# design.net
KiCad netlist of a schematic drawn in Altium Designer
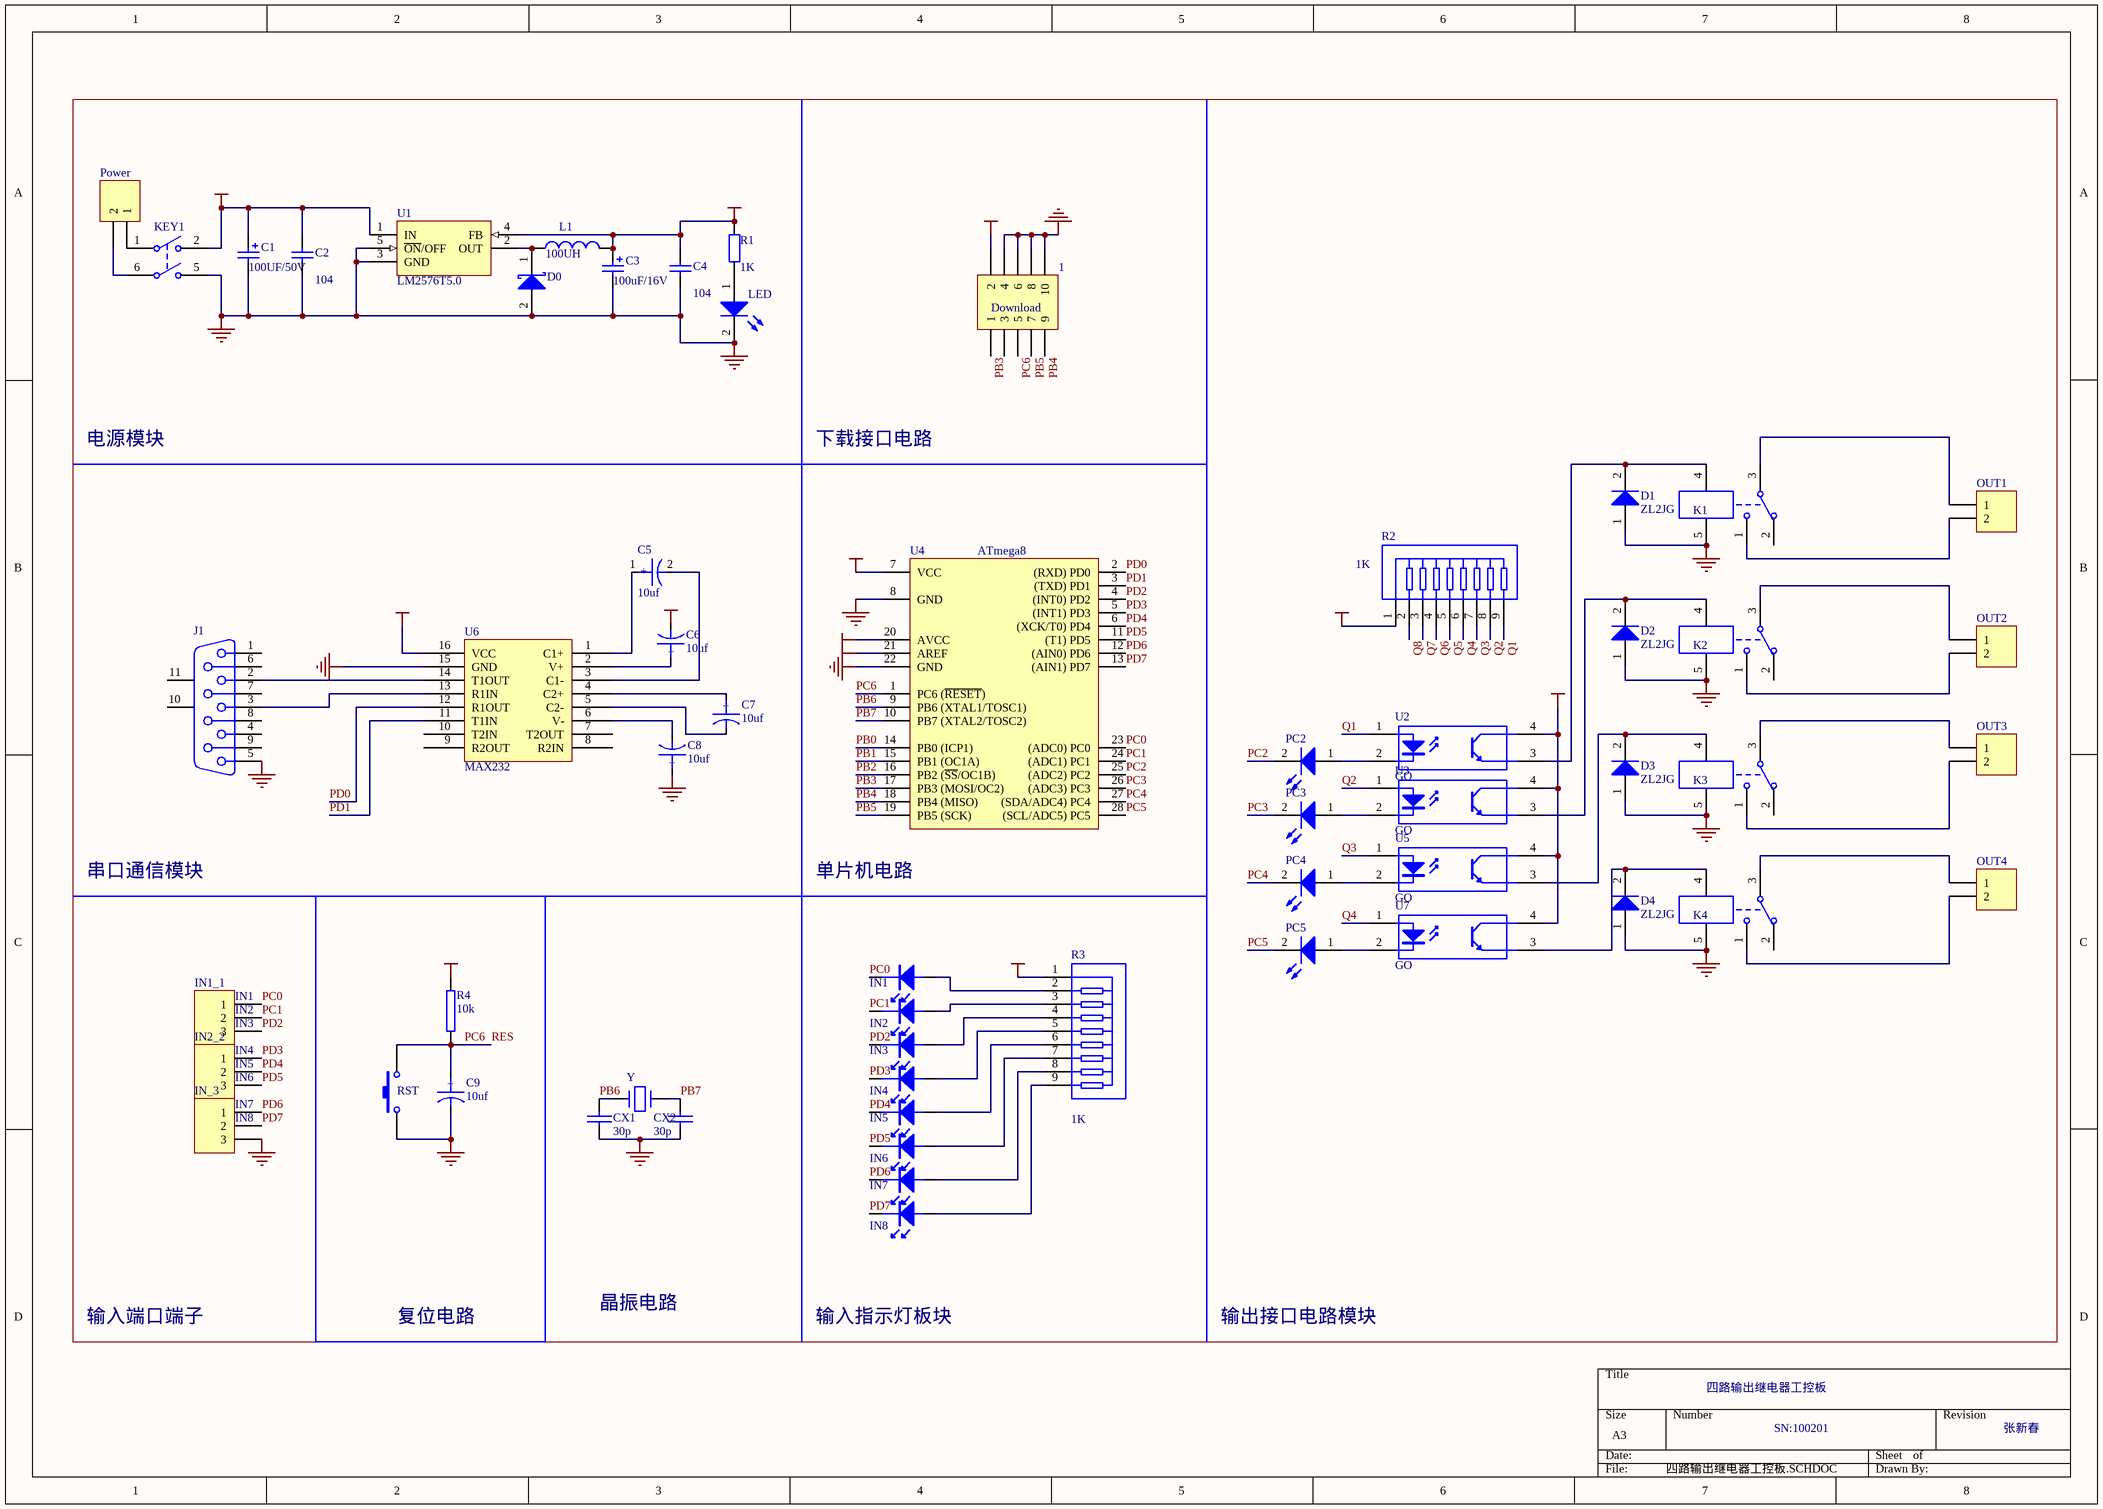
[diagram p0: 四路输出继电器工控板.SCHDOC]

(export (version "E")
  (design (tool "Eeschema 10.0.6"))
  (components
    (comp (ref "1")
      (value "Download")
      (footprint "HDR-2x5")
      (description "Header, 5-Pin, Dual row")
      (fields (field (name "PUBLISHER") "Altium Limited"))
      (libsource (lib "Miscellaneous Connectors") (part "Header 5X2"))
    )
    (comp (ref "C1")
      (value "100UF/50V")
      (footprint "C-DJ-6")
      (description "电解电容")
      (fields (field (name "Comment") "DJDR") (field (name "PUBLISHER") "Altium Limited"))
      (libsource (lib "zxcourhc") (part "DJDR"))
    )
    (comp (ref "C2")
      (value "104")
      (footprint "CPDR")
      (description "瓷片电容")
      (fields (field (name "Comment") "CPDR") (field (name "PUBLISHER") "Altium Limited"))
      (libsource (lib "zxcourhc") (part "CPDR"))
    )
    (comp (ref "C3")
      (value "100uF/16V")
      (footprint "C-DJ-6")
      (description "电解电容")
      (fields (field (name "Comment") "DJDR") (field (name "PUBLISHER") "Altium Limited"))
      (libsource (lib "zxcourhc") (part "DJDR"))
    )
    (comp (ref "C4")
      (value "104")
      (footprint "CPDR")
      (description "瓷片电容")
      (fields (field (name "Comment") "CPDR") (field (name "PUBLISHER") "Altium Limited"))
      (libsource (lib "zxcourhc") (part "CPDR"))
    )
    (comp (ref "C5")
      (value "10uf")
      (footprint "C-DJ-4")
      (description "Capacitor")
      (libsource (lib "*") (part "CAPACITOR POL"))
    )
    (comp (ref "C6")
      (value "10uf")
      (footprint "C-DJ-4")
      (description "Capacitor")
      (libsource (lib "") (part "CAPACITOR POL_1"))
    )
    (comp (ref "C7")
      (value "10uf")
      (footprint "C-DJ-4")
      (description "Capacitor")
      (libsource (lib "") (part "CAPACITOR POL_1"))
    )
    (comp (ref "C8")
      (value "10uf")
      (footprint "C-DJ-4")
      (description "Capacitor")
      (libsource (lib "") (part "CAPACITOR POL_1"))
    )
    (comp (ref "C9")
      (value "10uf")
      (footprint "C-DJ-4")
      (description "Capacitor")
      (libsource (lib "") (part "CAPACITOR POL_1"))
    )
    (comp (ref "CX1")
      (value "30p")
      (footprint "HDR1X2")
      (description "Capacitor")
      (libsource (lib "*") (part "CAP"))
    )
    (comp (ref "CX2")
      (value "30p")
      (footprint "HDR1X2")
      (description "Capacitor")
      (libsource (lib "*") (part "CAP"))
    )
    (comp (ref "D0")
      (value "WY2JG")
      (footprint "ZCDZL")
      (description "稳压二级管")
      (fields (field (name "PUBLISHER") "Altium Limited"))
      (libsource (lib "zxcourhc") (part "WY2JG"))
    )
    (comp (ref "D1")
      (value "ZL2JG")
      (footprint "D-ZL-10")
      (description "整流二极管")
      (fields (field (name "PUBLISHER") "Altium Limited"))
      (libsource (lib "zxcourhc") (part "ZL2JG"))
    )
    (comp (ref "D2")
      (value "ZL2JG")
      (footprint "D-ZL-10")
      (description "整流二极管")
      (fields (field (name "PUBLISHER") "Altium Limited"))
      (libsource (lib "zxcourhc") (part "ZL2JG"))
    )
    (comp (ref "D3")
      (value "ZL2JG")
      (footprint "D-ZL-10")
      (description "整流二极管")
      (fields (field (name "PUBLISHER") "Altium Limited"))
      (libsource (lib "zxcourhc") (part "ZL2JG"))
    )
    (comp (ref "D4")
      (value "ZL2JG")
      (footprint "D-ZL-10")
      (description "整流二极管")
      (fields (field (name "PUBLISHER") "Altium Limited"))
      (libsource (lib "zxcourhc") (part "ZL2JG"))
    )
    (comp (ref "IN1") (value "LED") (footprint "HDR1X2") (libsource (lib "OldCow1 (1)") (part "LED")))
    (comp (ref "IN1_1")
      (value "PZ_3")
      (footprint "JK128_3")
      (description "排针——3")
      (fields (field (name "PUBLISHER") "Altium Limited"))
      (libsource (lib "zxcourhc") (part "PZ_3"))
    )
    (comp (ref "IN2") (value "LED") (footprint "HDR1X2") (libsource (lib "OldCow1 (1)") (part "LED")))
    (comp (ref "IN2_2")
      (value "PZ_3")
      (footprint "JK128_3")
      (description "排针——3")
      (fields (field (name "PUBLISHER") "Altium Limited"))
      (libsource (lib "zxcourhc") (part "PZ_3"))
    )
    (comp (ref "IN3") (value "LED") (footprint "HDR1X2") (libsource (lib "OldCow1 (1)") (part "LED")))
    (comp (ref "IN4") (value "LED") (footprint "HDR1X2") (libsource (lib "OldCow1 (1)") (part "LED")))
    (comp (ref "IN5") (value "LED") (footprint "HDR1X2") (libsource (lib "OldCow1 (1)") (part "LED")))
    (comp (ref "IN6") (value "LED") (footprint "HDR1X2") (libsource (lib "OldCow1 (1)") (part "LED")))
    (comp (ref "IN7") (value "LED") (footprint "HDR1X2") (libsource (lib "OldCow1 (1)") (part "LED")))
    (comp (ref "IN8") (value "LED") (footprint "HDR1X2") (libsource (lib "OldCow1 (1)") (part "LED")))
    (comp (ref "IN_3")
      (value "~")
      (footprint "JK128_3")
      (description "排针——3")
      (fields (field (name "PUBLISHER") "Altium Limited"))
      (libsource (lib "zxcourhc") (part "PZ_3"))
    )
    (comp (ref "J1")
      (value "D Connector 9")
      (footprint "DSUB1.385-2H9")
      (description "Receptacle Assembly, 9 Position, Right Angle")
      (fields (field (name "PUBLISHER") "Altium Limited"))
      (libsource (lib "Miscellaneous Connectors") (part "D Connector 9"))
    )
    (comp (ref "K1")
      (value "JDQYCK")
      (footprint "JQC-3F/T73")
      (description "继电器——1常开1常闭")
      (fields (field (name "PUBLISHER") "Altium Limited"))
      (libsource (lib "zxcourhc") (part "JDQYCK"))
    )
    (comp (ref "K2")
      (value "JDQYCK")
      (footprint "JQC-3F/T73")
      (description "继电器——1常开1常闭")
      (fields (field (name "PUBLISHER") "Altium Limited"))
      (libsource (lib "zxcourhc") (part "JDQYCK"))
    )
    (comp (ref "K3")
      (value "JDQYCK")
      (footprint "JQC-3F/T73")
      (description "继电器——1常开1常闭")
      (fields (field (name "PUBLISHER") "Altium Limited"))
      (libsource (lib "zxcourhc") (part "JDQYCK"))
    )
    (comp (ref "K4")
      (value "JDQYCK")
      (footprint "JQC-3F/T73")
      (description "继电器——1常开1常闭")
      (fields (field (name "PUBLISHER") "Altium Limited"))
      (libsource (lib "zxcourhc") (part "JDQYCK"))
    )
    (comp (ref "KEY1")
      (value "SW-DPST")
      (footprint "DPDT-6")
      (description "Double-Pole, Single-Throw Switch")
      (fields (field (name "PUBLISHER") "Altium Limited"))
      (libsource (lib "Miscellaneous Devices") (part "SW-DPST"))
    )
    (comp (ref "L1")
      (value "100UH")
      (footprint "L_DG")
      (description "电感")
      (fields (field (name "Comment") "DG") (field (name "PUBLISHER") "Altium Limited"))
      (libsource (lib "zxcourhc") (part "DG"))
    )
    (comp (ref "LED")
      (value "LED")
      (footprint "LED_D")
      (description "发光二极管")
      (fields (field (name "PUBLISHER") "Altium Limited"))
      (libsource (lib "zxcourhc") (part "LED"))
    )
    (comp (ref "OUT1")
      (value "PZ_2")
      (footprint "DYDZ")
      (description "排针——2")
      (fields (field (name "PUBLISHER") "Altium Limited"))
      (libsource (lib "zxcourhc") (part "PZ_2"))
    )
    (comp (ref "OUT2")
      (value "PZ_2")
      (footprint "DYDZ")
      (description "排针——2")
      (fields (field (name "PUBLISHER") "Altium Limited"))
      (libsource (lib "zxcourhc") (part "PZ_2"))
    )
    (comp (ref "OUT3")
      (value "PZ_2")
      (footprint "DYDZ")
      (description "排针——2")
      (fields (field (name "PUBLISHER") "Altium Limited"))
      (libsource (lib "zxcourhc") (part "PZ_2"))
    )
    (comp (ref "OUT4")
      (value "PZ_2")
      (footprint "DYDZ")
      (description "排针——2")
      (fields (field (name "PUBLISHER") "Altium Limited"))
      (libsource (lib "zxcourhc") (part "PZ_2"))
    )
    (comp (ref "PC2")
      (value "~")
      (footprint "CPDR")
      (description "发光二极管")
      (fields (field (name "PUBLISHER") "Altium Limited"))
      (libsource (lib "zxcourhc") (part "LED"))
    )
    (comp (ref "PC3")
      (value "~")
      (footprint "CPDR")
      (description "发光二极管")
      (fields (field (name "PUBLISHER") "Altium Limited"))
      (libsource (lib "zxcourhc") (part "LED"))
    )
    (comp (ref "PC4")
      (value "~")
      (footprint "CPDR")
      (description "发光二极管")
      (fields (field (name "PUBLISHER") "Altium Limited"))
      (libsource (lib "zxcourhc") (part "LED"))
    )
    (comp (ref "PC5")
      (value "~")
      (footprint "CPDR")
      (description "发光二极管")
      (fields (field (name "PUBLISHER") "Altium Limited"))
      (libsource (lib "zxcourhc") (part "LED"))
    )
    (comp (ref "Power")
      (value "PZ_2")
      (footprint "JK128_2")
      (description "排针——2")
      (fields (field (name "PUBLISHER") "Altium Limited"))
      (libsource (lib "") (part "PZ_2_1"))
    )
    (comp (ref "R1")
      (value "1K")
      (footprint "RSE")
      (description "电阻")
      (fields (field (name "Comment") "Res") (field (name "PUBLISHER") "Altium Limited"))
      (libsource (lib "zxcourhc") (part "Res"))
    )
    (comp (ref "R2")
      (value "1K")
      (footprint "HDR-10")
      (description "8位排阻")
      (fields (field (name "PUBLISHER") "Altium Limited"))
      (libsource (lib "zxcourhc") (part "Res PZ_8"))
    )
    (comp (ref "R3")
      (value "1K")
      (footprint "HDR-10")
      (description "8位排阻")
      (fields (field (name "PUBLISHER") "Altium Limited"))
      (libsource (lib "zxcourhc") (part "Res PZ_8"))
    )
    (comp (ref "R4") (value "10k") (footprint "RSE") (libsource (lib "*") (part "RES2")))
    (comp (ref "RST")
      (value "~")
      (footprint "an-6*6")
      (description "Switch")
      (fields (field (name "PUBLISHER") "Altium Limited"))
      (libsource (lib "Miscellaneous Devices") (part "SW-PB"))
    )
    (comp (ref "U1")
      (value "LM2576T5.0")
      (footprint "LM2576")
      (description "Simple Switcher 3A Step Down Voltage Regulator")
      (fields (field (name "PUBLISHER") "Altium Limited"))
      (libsource (lib "NSC Power Mgt Switching Regulator") (part "LM2576HVT-3.3"))
    )
    (comp (ref "U2")
      (value "GO")
      (footprint "DIP-4")
      (description "光耦")
      (fields (field (name "PUBLISHER") "Altium Limited"))
      (libsource (lib "zxcourhc") (part "GO"))
    )
    (comp (ref "U3")
      (value "GO")
      (footprint "DIP-4")
      (description "光耦")
      (fields (field (name "PUBLISHER") "Altium Limited"))
      (libsource (lib "zxcourhc") (part "GO"))
    )
    (comp (ref "U4")
      (value "ATmega8")
      (footprint "DIP-28")
      (description "8 位微处理器/28引脚")
      (fields (field (name "发布者") "磊元工作室"))
      (libsource (lib "MCU") (part "ATmega8-P"))
    )
    (comp (ref "U5")
      (value "GO")
      (footprint "DIP-4")
      (description "光耦")
      (fields (field (name "PUBLISHER") "Altium Limited"))
      (libsource (lib "zxcourhc") (part "GO"))
    )
    (comp (ref "U6") (value "MAX232") (footprint "DIP16") (libsource (lib "*") (part "MAX232")))
    (comp (ref "U7")
      (value "GO")
      (footprint "DIP-4")
      (description "光耦")
      (fields (field (name "PUBLISHER") "Altium Limited"))
      (libsource (lib "zxcourhc") (part "GO"))
    )
    (comp (ref "Y1")
      (value "Y")
      (footprint "JZ_ZC")
      (description "Crystal")
      (libsource (lib "*") (part "CRYSTAL"))
    )
  )
  (nets
    (net (code "1") (name "+12V") (class "Default")
      (node (ref "C1") (pin "1") (pinfunction "1_1") (pintype "passive"))
      (node (ref "C2") (pin "2") (pinfunction "2_2") (pintype "passive"))
      (node (ref "KEY1") (pin "2") (pinfunction "NO1_2") (pintype "passive"))
      (node (ref "U1") (pin "1") (pinfunction "IN_1") (pintype "power_in"))
      (node (ref "U2") (pin "4") (pinfunction "C_4") (pintype "passive"))
      (node (ref "U3") (pin "4") (pinfunction "C_4") (pintype "passive"))
      (node (ref "U5") (pin "4") (pinfunction "C_4") (pintype "passive"))
      (node (ref "U7") (pin "4") (pinfunction "C_4") (pintype "passive"))
    )
    (net (code "2") (name "/PB0") (class "Default")
      (node (ref "U4") (pin "14") (pinfunction "PB0_(ICP1)_14") (pintype "passive"))
    )
    (net (code "3") (name "/PB1") (class "Default")
      (node (ref "U4") (pin "15") (pinfunction "PB1_(OC1A)_15") (pintype "passive"))
    )
    (net (code "4") (name "/PB2") (class "Default")
      (node (ref "U4") (pin "16") (pinfunction "PB2_(~{SS}/OC1B)_16") (pintype "passive"))
    )
    (net (code "5") (name "/PB3") (class "Default")
      (node (ref "1") (pin "1") (pinfunction "1_1") (pintype "passive"))
      (node (ref "U4") (pin "17") (pinfunction "PB3_(MOSI/OC2)_17") (pintype "passive"))
    )
    (net (code "6") (name "/PB4") (class "Default")
      (node (ref "1") (pin "9") (pinfunction "9_9") (pintype "passive"))
      (node (ref "U4") (pin "18") (pinfunction "PB4_(MISO)_18") (pintype "passive"))
    )
    (net (code "7") (name "/PB5") (class "Default")
      (node (ref "1") (pin "7") (pinfunction "7_7") (pintype "passive"))
      (node (ref "U4") (pin "19") (pinfunction "PB5_(SCK)_19") (pintype "passive"))
    )
    (net (code "8") (name "/PB6") (class "Default")
      (node (ref "CX1") (pin "1") (pinfunction "1_1") (pintype "passive"))
      (node (ref "U4") (pin "9") (pinfunction "PB6_(XTAL1/TOSC1)_9") (pintype "passive"))
      (node (ref "Y1") (pin "2") (pinfunction "2_2") (pintype "passive"))
    )
    (net (code "9") (name "/PB7") (class "Default")
      (node (ref "CX2") (pin "1") (pinfunction "1_1") (pintype "passive"))
      (node (ref "U4") (pin "10") (pinfunction "PB7_(XTAL2/TOSC2)_10") (pintype "passive"))
      (node (ref "Y1") (pin "1") (pinfunction "1_1") (pintype "passive"))
    )
    (net (code "10") (name "/PC0") (class "Default")
      (node (ref "IN1") (pin "2") (pinfunction "K_2") (pintype "passive"))
      (node (ref "IN1_1") (pin "1") (pinfunction "1_1") (pintype "passive"))
      (node (ref "U4") (pin "23") (pinfunction "(ADC0)_PC0_23") (pintype "passive"))
    )
    (net (code "11") (name "/PC1") (class "Default")
      (node (ref "IN1_1") (pin "2") (pinfunction "2_2") (pintype "passive"))
      (node (ref "IN2") (pin "2") (pinfunction "K_2") (pintype "passive"))
      (node (ref "U4") (pin "24") (pinfunction "(ADC1)_PC1_24") (pintype "passive"))
    )
    (net (code "12") (name "/PC2") (class "Default")
      (node (ref "PC2") (pin "2") (pinfunction "K_2") (pintype "passive"))
      (node (ref "U4") (pin "25") (pinfunction "(ADC2)_PC2_25") (pintype "passive"))
    )
    (net (code "13") (name "/PC3") (class "Default")
      (node (ref "PC3") (pin "2") (pinfunction "K_2") (pintype "passive"))
      (node (ref "U4") (pin "26") (pinfunction "(ADC3)_PC3_26") (pintype "passive"))
    )
    (net (code "14") (name "/PC4") (class "Default")
      (node (ref "PC4") (pin "2") (pinfunction "K_2") (pintype "passive"))
      (node (ref "U4") (pin "27") (pinfunction "(SDA/ADC4)_PC4_27") (pintype "passive"))
    )
    (net (code "15") (name "/PC5") (class "Default")
      (node (ref "PC5") (pin "2") (pinfunction "K_2") (pintype "passive"))
      (node (ref "U4") (pin "28") (pinfunction "(SCL/ADC5)_PC5_28") (pintype "passive"))
    )
    (net (code "16") (name "/PC6") (class "Default")
      (node (ref "1") (pin "5") (pinfunction "5_5") (pintype "passive"))
      (node (ref "C9") (pin "1") (pinfunction "1_1") (pintype "passive"))
      (node (ref "R4") (pin "1") (pinfunction "1_1") (pintype "passive"))
      (node (ref "RST") (pin "1") (pinfunction "1_1") (pintype "passive"))
      (node (ref "U4") (pin "1") (pinfunction "PC6_(~{RESET})_1") (pintype "passive"))
    )
    (net (code "17") (name "/PD0") (class "Default")
      (node (ref "U4") (pin "2") (pinfunction "(RXD)_PD0_2") (pintype "passive"))
      (node (ref "U6") (pin "12") (pinfunction "R1OUT_12") (pintype "passive"))
    )
    (net (code "18") (name "/PD1") (class "Default")
      (node (ref "U4") (pin "3") (pinfunction "(TXD)_PD1_3") (pintype "passive"))
      (node (ref "U6") (pin "11") (pinfunction "T1IN_11") (pintype "passive"))
    )
    (net (code "19") (name "/PD2") (class "Default")
      (node (ref "IN1_1") (pin "3") (pinfunction "3_3") (pintype "passive"))
      (node (ref "IN3") (pin "2") (pinfunction "K_2") (pintype "passive"))
      (node (ref "U4") (pin "4") (pinfunction "(INT0)_PD2_4") (pintype "passive"))
    )
    (net (code "20") (name "/PD3") (class "Default")
      (node (ref "IN2_2") (pin "1") (pinfunction "1_1") (pintype "passive"))
      (node (ref "IN4") (pin "2") (pinfunction "K_2") (pintype "passive"))
      (node (ref "U4") (pin "5") (pinfunction "(INT1)_PD3_5") (pintype "passive"))
    )
    (net (code "21") (name "/PD4") (class "Default")
      (node (ref "IN2_2") (pin "2") (pinfunction "2_2") (pintype "passive"))
      (node (ref "IN5") (pin "2") (pinfunction "K_2") (pintype "passive"))
      (node (ref "U4") (pin "6") (pinfunction "(XCK/T0)_PD4_6") (pintype "passive"))
    )
    (net (code "22") (name "/PD5") (class "Default")
      (node (ref "IN2_2") (pin "3") (pinfunction "3_3") (pintype "passive"))
      (node (ref "IN6") (pin "2") (pinfunction "K_2") (pintype "passive"))
      (node (ref "U4") (pin "11") (pinfunction "(T1)_PD5_11") (pintype "passive"))
    )
    (net (code "23") (name "/PD6") (class "Default")
      (node (ref "IN7") (pin "2") (pinfunction "K_2") (pintype "passive"))
      (node (ref "IN_3") (pin "1") (pinfunction "1_1") (pintype "passive"))
      (node (ref "U4") (pin "12") (pinfunction "(AIN0)_PD6_12") (pintype "passive"))
    )
    (net (code "24") (name "/PD7") (class "Default")
      (node (ref "IN8") (pin "2") (pinfunction "K_2") (pintype "passive"))
      (node (ref "IN_3") (pin "2") (pinfunction "2_2") (pintype "passive"))
      (node (ref "U4") (pin "13") (pinfunction "(AIN1)_PD7_13") (pintype "passive"))
    )
    (net (code "25") (name "/Q1") (class "Default")
      (node (ref "R2") (pin "9") (pinfunction "9_9") (pintype "passive"))
      (node (ref "U2") (pin "1") (pinfunction "A_1") (pintype "passive"))
    )
    (net (code "26") (name "/Q2") (class "Default")
      (node (ref "R2") (pin "8") (pinfunction "8_8") (pintype "passive"))
      (node (ref "U3") (pin "1") (pinfunction "A_1") (pintype "passive"))
    )
    (net (code "27") (name "/Q3") (class "Default")
      (node (ref "R2") (pin "7") (pinfunction "7_7") (pintype "passive"))
      (node (ref "U5") (pin "1") (pinfunction "A_1") (pintype "passive"))
    )
    (net (code "28") (name "/Q4") (class "Default")
      (node (ref "R2") (pin "6") (pinfunction "6_6") (pintype "passive"))
      (node (ref "U7") (pin "1") (pinfunction "A_1") (pintype "passive"))
    )
    (net (code "29") (name "/Q5") (class "Default")
      (node (ref "R2") (pin "5") (pinfunction "5_5") (pintype "passive"))
    )
    (net (code "30") (name "/Q6") (class "Default")
      (node (ref "R2") (pin "4") (pinfunction "4_4") (pintype "passive"))
    )
    (net (code "31") (name "/Q7") (class "Default")
      (node (ref "R2") (pin "3") (pinfunction "3_3") (pintype "passive"))
    )
    (net (code "32") (name "/Q8") (class "Default")
      (node (ref "R2") (pin "2") (pinfunction "2_2") (pintype "passive"))
    )
    (net (code "33") (name "GND") (class "Default")
      (node (ref "1") (pin "10") (pinfunction "10_10") (pintype "passive"))
      (node (ref "1") (pin "4") (pinfunction "4_4") (pintype "passive"))
      (node (ref "1") (pin "6") (pinfunction "6_6") (pintype "passive"))
      (node (ref "1") (pin "8") (pinfunction "8_8") (pintype "passive"))
      (node (ref "C1") (pin "2") (pinfunction "2_2") (pintype "passive"))
      (node (ref "C2") (pin "1") (pinfunction "1_1") (pintype "passive"))
      (node (ref "C3") (pin "2") (pinfunction "2_2") (pintype "passive"))
      (node (ref "C4") (pin "1") (pinfunction "1_1") (pintype "passive"))
      (node (ref "C8") (pin "1") (pinfunction "1_1") (pintype "passive"))
      (node (ref "C9") (pin "2") (pinfunction "2_2") (pintype "passive"))
      (node (ref "CX1") (pin "2") (pinfunction "2_2") (pintype "passive"))
      (node (ref "CX2") (pin "2") (pinfunction "2_2") (pintype "passive"))
      (node (ref "D0") (pin "2") (pinfunction "K_2") (pintype "passive"))
      (node (ref "D1") (pin "1") (pinfunction "A_1") (pintype "passive"))
      (node (ref "D2") (pin "1") (pinfunction "A_1") (pintype "passive"))
      (node (ref "D3") (pin "1") (pinfunction "A_1") (pintype "passive"))
      (node (ref "D4") (pin "1") (pinfunction "A_1") (pintype "passive"))
      (node (ref "IN_3") (pin "3") (pinfunction "3_3") (pintype "passive"))
      (node (ref "J1") (pin "5") (pinfunction "5_5") (pintype "passive"))
      (node (ref "K1") (pin "5") (pinfunction "5_5") (pintype "passive"))
      (node (ref "K2") (pin "5") (pinfunction "5_5") (pintype "passive"))
      (node (ref "K3") (pin "5") (pinfunction "5_5") (pintype "passive"))
      (node (ref "K4") (pin "5") (pinfunction "5_5") (pintype "passive"))
      (node (ref "KEY1") (pin "5") (pinfunction "NO2_5") (pintype "passive"))
      (node (ref "LED") (pin "2") (pinfunction "K_2") (pintype "passive"))
      (node (ref "RST") (pin "2") (pinfunction "2_2") (pintype "passive"))
      (node (ref "U1") (pin "3") (pinfunction "GND_3") (pintype "power_in"))
      (node (ref "U1") (pin "5") (pinfunction "~{ON}/OFF_5") (pintype "input"))
      (node (ref "U4") (pin "22") (pinfunction "GND_22") (pintype "passive"))
      (node (ref "U4") (pin "8") (pinfunction "GND_8") (pintype "passive"))
      (node (ref "U6") (pin "15") (pinfunction "GND_15") (pintype "passive"))
    )
    (net (code "34") (name "Net-(D0-A)") (class "Default")
      (node (ref "D0") (pin "1") (pinfunction "A_1") (pintype "passive"))
      (node (ref "L1") (pin "1") (pinfunction "1_1") (pintype "passive"))
      (node (ref "U1") (pin "2") (pinfunction "OUT_2") (pintype "power_in"))
    )
    (net (code "35") (name "Net-(D1-K)") (class "Default")
      (node (ref "D1") (pin "2") (pinfunction "K_2") (pintype "passive"))
      (node (ref "K1") (pin "4") (pinfunction "4_4") (pintype "passive"))
      (node (ref "U2") (pin "3") (pinfunction "E_3") (pintype "passive"))
    )
    (net (code "36") (name "Net-(D2-K)") (class "Default")
      (node (ref "D2") (pin "2") (pinfunction "K_2") (pintype "passive"))
      (node (ref "K2") (pin "4") (pinfunction "4_4") (pintype "passive"))
      (node (ref "U3") (pin "3") (pinfunction "E_3") (pintype "passive"))
    )
    (net (code "37") (name "Net-(D3-K)") (class "Default")
      (node (ref "D3") (pin "2") (pinfunction "K_2") (pintype "passive"))
      (node (ref "K3") (pin "4") (pinfunction "4_4") (pintype "passive"))
      (node (ref "U5") (pin "3") (pinfunction "E_3") (pintype "passive"))
    )
    (net (code "38") (name "Net-(D4-K)") (class "Default")
      (node (ref "D4") (pin "2") (pinfunction "K_2") (pintype "passive"))
      (node (ref "K4") (pin "4") (pinfunction "4_4") (pintype "passive"))
      (node (ref "U7") (pin "3") (pinfunction "E_3") (pintype "passive"))
    )
    (net (code "39") (name "Net-(IN1-A)") (class "Default")
      (node (ref "IN1") (pin "1") (pinfunction "A_1") (pintype "passive"))
      (node (ref "R3") (pin "2") (pinfunction "2_2") (pintype "passive"))
    )
    (net (code "40") (name "Net-(IN2-A)") (class "Default")
      (node (ref "IN2") (pin "1") (pinfunction "A_1") (pintype "passive"))
      (node (ref "R3") (pin "3") (pinfunction "3_3") (pintype "passive"))
    )
    (net (code "41") (name "Net-(IN3-A)") (class "Default")
      (node (ref "IN3") (pin "1") (pinfunction "A_1") (pintype "passive"))
      (node (ref "R3") (pin "4") (pinfunction "4_4") (pintype "passive"))
    )
    (net (code "42") (name "Net-(IN4-A)") (class "Default")
      (node (ref "IN4") (pin "1") (pinfunction "A_1") (pintype "passive"))
      (node (ref "R3") (pin "5") (pinfunction "5_5") (pintype "passive"))
    )
    (net (code "43") (name "Net-(IN5-A)") (class "Default")
      (node (ref "IN5") (pin "1") (pinfunction "A_1") (pintype "passive"))
      (node (ref "R3") (pin "6") (pinfunction "6_6") (pintype "passive"))
    )
    (net (code "44") (name "Net-(IN6-A)") (class "Default")
      (node (ref "IN6") (pin "1") (pinfunction "A_1") (pintype "passive"))
      (node (ref "R3") (pin "7") (pinfunction "7_7") (pintype "passive"))
    )
    (net (code "45") (name "Net-(IN7-A)") (class "Default")
      (node (ref "IN7") (pin "1") (pinfunction "A_1") (pintype "passive"))
      (node (ref "R3") (pin "8") (pinfunction "8_8") (pintype "passive"))
    )
    (net (code "46") (name "Net-(IN8-A)") (class "Default")
      (node (ref "IN8") (pin "1") (pinfunction "A_1") (pintype "passive"))
      (node (ref "R3") (pin "9") (pinfunction "9_9") (pintype "passive"))
    )
    (net (code "47") (name "Net-(K1-Pad1)") (class "Default")
      (node (ref "K1") (pin "1") (pinfunction "1_1") (pintype "passive"))
      (node (ref "OUT1") (pin "2") (pinfunction "2_2") (pintype "passive"))
    )
    (net (code "48") (name "Net-(K1-Pad3)") (class "Default")
      (node (ref "K1") (pin "3") (pinfunction "3_3") (pintype "passive"))
      (node (ref "OUT1") (pin "1") (pinfunction "1_1") (pintype "passive"))
    )
    (net (code "49") (name "Net-(K2-Pad1)") (class "Default")
      (node (ref "K2") (pin "1") (pinfunction "1_1") (pintype "passive"))
      (node (ref "OUT2") (pin "2") (pinfunction "2_2") (pintype "passive"))
    )
    (net (code "50") (name "Net-(K2-Pad3)") (class "Default")
      (node (ref "K2") (pin "3") (pinfunction "3_3") (pintype "passive"))
      (node (ref "OUT2") (pin "1") (pinfunction "1_1") (pintype "passive"))
    )
    (net (code "51") (name "Net-(K3-Pad1)") (class "Default")
      (node (ref "K3") (pin "1") (pinfunction "1_1") (pintype "passive"))
      (node (ref "OUT3") (pin "2") (pinfunction "2_2") (pintype "passive"))
    )
    (net (code "52") (name "Net-(K3-Pad3)") (class "Default")
      (node (ref "K3") (pin "3") (pinfunction "3_3") (pintype "passive"))
      (node (ref "OUT3") (pin "1") (pinfunction "1_1") (pintype "passive"))
    )
    (net (code "53") (name "Net-(K4-Pad1)") (class "Default")
      (node (ref "K4") (pin "1") (pinfunction "1_1") (pintype "passive"))
      (node (ref "OUT4") (pin "2") (pinfunction "2_2") (pintype "passive"))
    )
    (net (code "54") (name "Net-(K4-Pad3)") (class "Default")
      (node (ref "K4") (pin "3") (pinfunction "3_3") (pintype "passive"))
      (node (ref "OUT4") (pin "1") (pinfunction "1_1") (pintype "passive"))
    )
    (net (code "55") (name "Net-(KEY1-COMMON1)") (class "Default")
      (node (ref "KEY1") (pin "1") (pinfunction "COMMON1_1") (pintype "passive"))
      (node (ref "Power") (pin "1") (pinfunction "1_1") (pintype "passive"))
    )
    (net (code "56") (name "Net-(KEY1-COMMON2)") (class "Default")
      (node (ref "KEY1") (pin "6") (pinfunction "COMMON2_6") (pintype "passive"))
      (node (ref "Power") (pin "2") (pinfunction "2_2") (pintype "passive"))
    )
    (net (code "57") (name "Net-(LED-A)") (class "Default")
      (node (ref "LED") (pin "1") (pinfunction "A_1") (pintype "passive"))
      (node (ref "R1") (pin "1") (pinfunction "1_1") (pintype "passive"))
    )
    (net (code "58") (name "Net-(PC2-A)") (class "Default")
      (node (ref "PC2") (pin "1") (pinfunction "A_1") (pintype "passive"))
      (node (ref "U2") (pin "2") (pinfunction "K_2") (pintype "passive"))
    )
    (net (code "59") (name "Net-(PC3-A)") (class "Default")
      (node (ref "PC3") (pin "1") (pinfunction "A_1") (pintype "passive"))
      (node (ref "U3") (pin "2") (pinfunction "K_2") (pintype "passive"))
    )
    (net (code "60") (name "Net-(PC4-A)") (class "Default")
      (node (ref "PC4") (pin "1") (pinfunction "A_1") (pintype "passive"))
      (node (ref "U5") (pin "2") (pinfunction "K_2") (pintype "passive"))
    )
    (net (code "61") (name "Net-(PC5-A)") (class "Default")
      (node (ref "PC5") (pin "1") (pinfunction "A_1") (pintype "passive"))
      (node (ref "U7") (pin "2") (pinfunction "K_2") (pintype "passive"))
    )
    (net (code "62") (name "Net-(U6-C1+)") (class "Default")
      (node (ref "C5") (pin "1") (pinfunction "1_1") (pintype "passive"))
      (node (ref "U6") (pin "1") (pinfunction "C1+_1") (pintype "passive"))
    )
    (net (code "63") (name "Net-(U6-C1-)") (class "Default")
      (node (ref "C5") (pin "2") (pinfunction "2_2") (pintype "passive"))
      (node (ref "U6") (pin "3") (pinfunction "C1-_3") (pintype "passive"))
    )
    (net (code "64") (name "Net-(U6-C2+)") (class "Default")
      (node (ref "C7") (pin "1") (pinfunction "1_1") (pintype "passive"))
      (node (ref "U6") (pin "4") (pinfunction "C2+_4") (pintype "passive"))
    )
    (net (code "65") (name "Net-(U6-C2-)") (class "Default")
      (node (ref "C7") (pin "2") (pinfunction "2_2") (pintype "passive"))
      (node (ref "U6") (pin "5") (pinfunction "C2-_5") (pintype "passive"))
    )
    (net (code "66") (name "Net-(U6-R1IN)") (class "Default")
      (node (ref "J1") (pin "3") (pinfunction "3_3") (pintype "passive"))
      (node (ref "U6") (pin "13") (pinfunction "R1IN_13") (pintype "passive"))
    )
    (net (code "67") (name "Net-(U6-T1OUT)") (class "Default")
      (node (ref "J1") (pin "2") (pinfunction "2_2") (pintype "passive"))
      (node (ref "U6") (pin "14") (pinfunction "T1OUT_14") (pintype "passive"))
    )
    (net (code "68") (name "Net-(U6-V+)") (class "Default")
      (node (ref "C6") (pin "1") (pinfunction "1_1") (pintype "passive"))
      (node (ref "U6") (pin "2") (pinfunction "V+_2") (pintype "passive"))
    )
    (net (code "69") (name "Net-(U6-V-)") (class "Default")
      (node (ref "C8") (pin "2") (pinfunction "2_2") (pintype "passive"))
      (node (ref "U6") (pin "6") (pinfunction "V-_6") (pintype "passive"))
    )
    (net (code "70") (name "VCC") (class "Default")
      (node (ref "1") (pin "2") (pinfunction "2_2") (pintype "passive"))
      (node (ref "C3") (pin "1") (pinfunction "1_1") (pintype "passive"))
      (node (ref "C4") (pin "2") (pinfunction "2_2") (pintype "passive"))
      (node (ref "C6") (pin "2") (pinfunction "2_2") (pintype "passive"))
      (node (ref "L1") (pin "2") (pinfunction "2_2") (pintype "passive"))
      (node (ref "R1") (pin "2") (pinfunction "2_2") (pintype "passive"))
      (node (ref "R2") (pin "1") (pinfunction "1_1") (pintype "passive"))
      (node (ref "R3") (pin "1") (pinfunction "1_1") (pintype "passive"))
      (node (ref "R4") (pin "2") (pinfunction "2_2") (pintype "passive"))
      (node (ref "U1") (pin "4") (pinfunction "FB_4") (pintype "input"))
      (node (ref "U4") (pin "20") (pinfunction "AVCC_20") (pintype "passive"))
      (node (ref "U4") (pin "21") (pinfunction "AREF_21") (pintype "passive"))
      (node (ref "U4") (pin "7") (pinfunction "VCC_7") (pintype "passive"))
      (node (ref "U6") (pin "16") (pinfunction "VCC_16") (pintype "passive"))
    )
    (net (code "71") (name "unconnected-(1-Pad3)") (class "Default")
      (node (ref "1") (pin "3") (pinfunction "3_3") (pintype "passive"))
    )
    (net (code "72") (name "unconnected-(J1-MH1-Pad10)") (class "Default")
      (node (ref "J1") (pin "10") (pinfunction "MH1_10") (pintype "passive"))
    )
    (net (code "73") (name "unconnected-(J1-MH2-Pad11)") (class "Default")
      (node (ref "J1") (pin "11") (pinfunction "MH2_11") (pintype "passive"))
    )
    (net (code "74") (name "unconnected-(J1-Pad1)") (class "Default")
      (node (ref "J1") (pin "1") (pinfunction "1_1") (pintype "passive"))
    )
    (net (code "75") (name "unconnected-(J1-Pad4)") (class "Default")
      (node (ref "J1") (pin "4") (pinfunction "4_4") (pintype "passive"))
    )
    (net (code "76") (name "unconnected-(J1-Pad6)") (class "Default")
      (node (ref "J1") (pin "6") (pinfunction "6_6") (pintype "passive"))
    )
    (net (code "77") (name "unconnected-(J1-Pad7)") (class "Default")
      (node (ref "J1") (pin "7") (pinfunction "7_7") (pintype "passive"))
    )
    (net (code "78") (name "unconnected-(J1-Pad8)") (class "Default")
      (node (ref "J1") (pin "8") (pinfunction "8_8") (pintype "passive"))
    )
    (net (code "79") (name "unconnected-(J1-Pad9)") (class "Default")
      (node (ref "J1") (pin "9") (pinfunction "9_9") (pintype "passive"))
    )
    (net (code "80") (name "unconnected-(K1-Pad2)") (class "Default")
      (node (ref "K1") (pin "2") (pinfunction "2_2") (pintype "passive"))
    )
    (net (code "81") (name "unconnected-(K2-Pad2)") (class "Default")
      (node (ref "K2") (pin "2") (pinfunction "2_2") (pintype "passive"))
    )
    (net (code "82") (name "unconnected-(K3-Pad2)") (class "Default")
      (node (ref "K3") (pin "2") (pinfunction "2_2") (pintype "passive"))
    )
    (net (code "83") (name "unconnected-(K4-Pad2)") (class "Default")
      (node (ref "K4") (pin "2") (pinfunction "2_2") (pintype "passive"))
    )
    (net (code "84") (name "unconnected-(U6-R2IN-Pad8)") (class "Default")
      (node (ref "U6") (pin "8") (pinfunction "R2IN_8") (pintype "passive"))
    )
    (net (code "85") (name "unconnected-(U6-R2OUT-Pad9)") (class "Default")
      (node (ref "U6") (pin "9") (pinfunction "R2OUT_9") (pintype "passive"))
    )
    (net (code "86") (name "unconnected-(U6-T2IN-Pad10)") (class "Default")
      (node (ref "U6") (pin "10") (pinfunction "T2IN_10") (pintype "passive"))
    )
    (net (code "87") (name "unconnected-(U6-T2OUT-Pad7)") (class "Default")
      (node (ref "U6") (pin "7") (pinfunction "T2OUT_7") (pintype "passive"))
    )
  )
)
